# 5_External_interface.net
KiCad netlist of a schematic drawn in Altium Designer
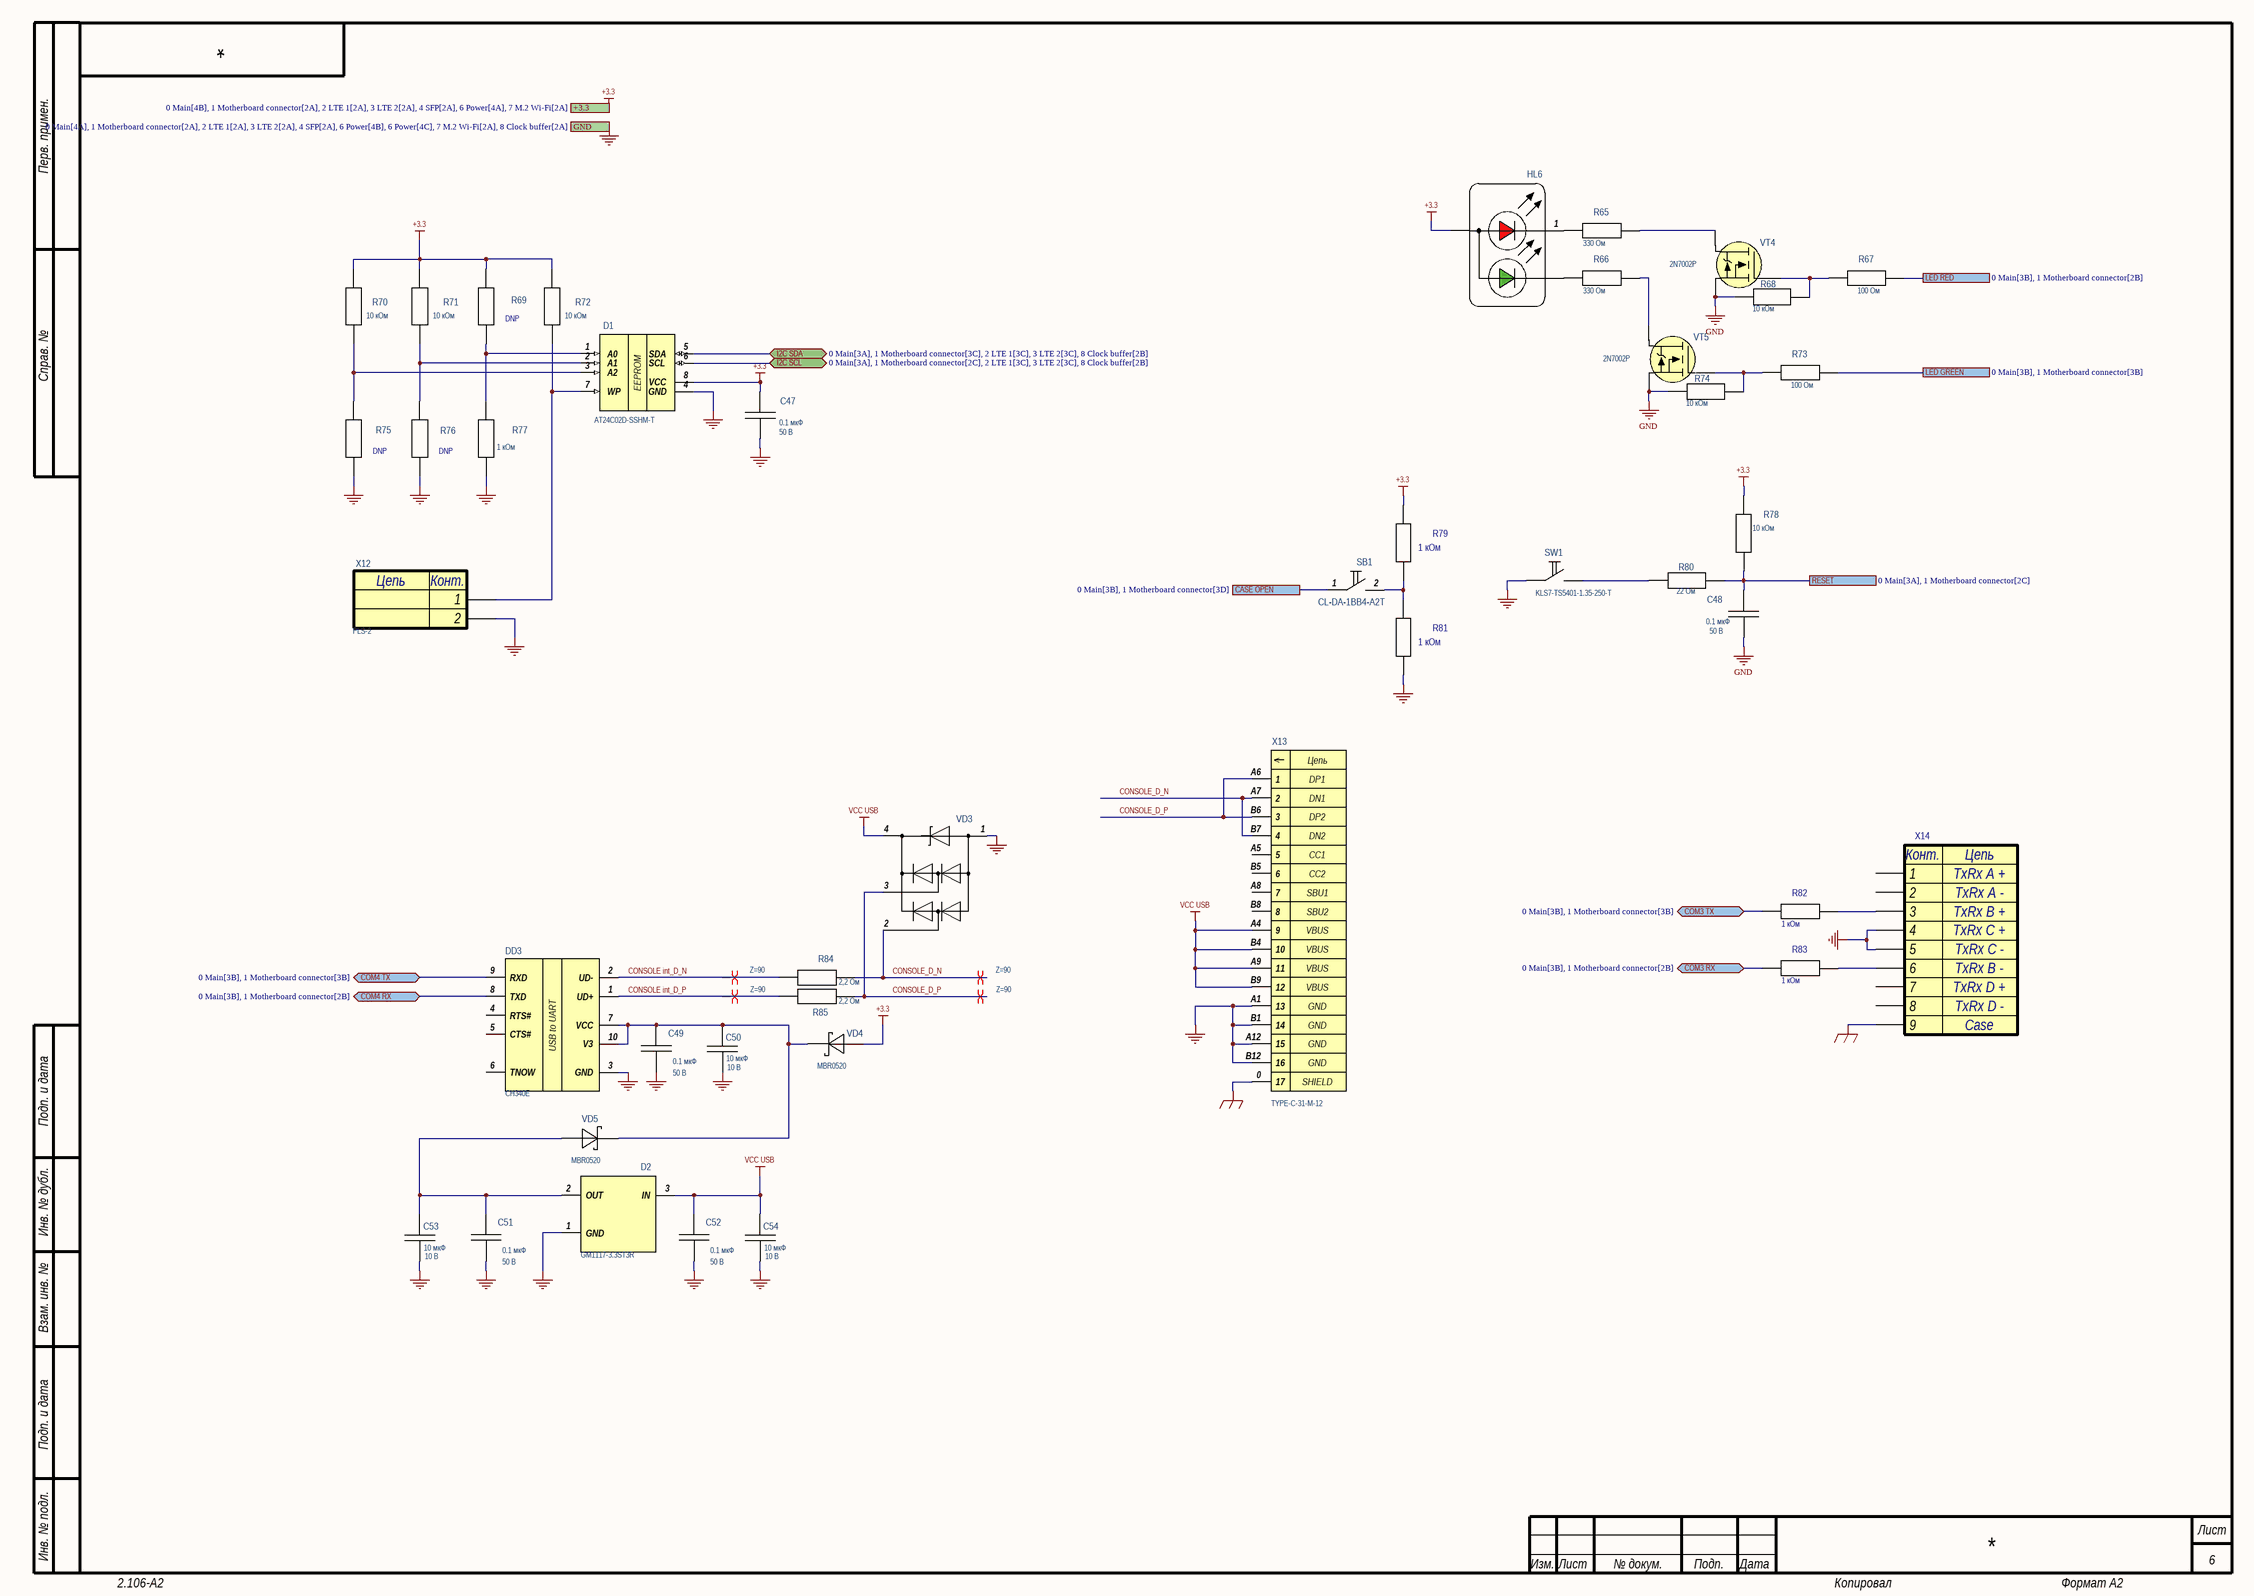
[diagram p0: 5 External interface.SchDoc]

(export (version "E")
  (design (tool "Eeschema 10.0.6"))
  (components
    (comp (ref "C47")
      (value "0.1 мкФ")
      (footprint "CAP_0402")
      (description "Конденсатор CHIP-0402 0.1 мкФ 50 В 10% X7R")
      (fields
        (field (name "PARTNUMBER") "CC0402KRX7R9BB104")
        (field (name "TOLERANCE") "10%")
        (field (name "НАПРЯЖЕНИЕ") "50 В")
        (field (name "AUTOR") "Admin")
      )
      (libsource (lib "Database_Altium") (part "STD_CAP"))
    )
    (comp (ref "C48")
      (value "0.1 мкФ")
      (footprint "CAP_0402")
      (description "Конденсатор CHIP-0402 0.1 мкФ 50 В 10% X7R")
      (fields
        (field (name "PARTNUMBER") "CC0402KRX7R9BB104")
        (field (name "TOLERANCE") "10%")
        (field (name "НАПРЯЖЕНИЕ") "50 В")
        (field (name "AUTOR") "Admin")
      )
      (libsource (lib "Database_Altium") (part "STD_CAP"))
    )
    (comp (ref "C49")
      (value "0.1 мкФ")
      (footprint "CAP_0402")
      (description "Конденсатор CHIP-0402 0.1 мкФ 50 В 10% X7R")
      (fields
        (field (name "PARTNUMBER") "CC0402KRX7R9BB104")
        (field (name "TOLERANCE") "10%")
        (field (name "НАПРЯЖЕНИЕ") "50 В")
        (field (name "AUTOR") "Admin")
      )
      (libsource (lib "Database_Altium") (part "STD_CAP"))
    )
    (comp (ref "C50")
      (value "10 мкФ")
      (footprint "CAP_0603")
      (description "Конденсатор CHIP-0603 10 мкФ 10 В 10% X7R")
      (fields
        (field (name "PARTNUMBER") "GRM188Z71A106KA73D")
        (field (name "TOLERANCE") "10%")
        (field (name "НАПРЯЖЕНИЕ") "10 В")
        (field (name "AUTOR") "Admin")
      )
      (libsource (lib "Database_Altium") (part "STD_CAP"))
    )
    (comp (ref "C51")
      (value "0.1 мкФ")
      (footprint "CAP_0402")
      (description "Конденсатор CHIP-0402 0.1 мкФ 50 В 10% X7R")
      (fields
        (field (name "PARTNUMBER") "CC0402KRX7R9BB104")
        (field (name "TOLERANCE") "10%")
        (field (name "НАПРЯЖЕНИЕ") "50 В")
        (field (name "AUTOR") "Admin")
      )
      (libsource (lib "Database_Altium") (part "STD_CAP"))
    )
    (comp (ref "C52")
      (value "0.1 мкФ")
      (footprint "CAP_0402")
      (description "Конденсатор CHIP-0402 0.1 мкФ 50 В 10% X7R")
      (fields
        (field (name "PARTNUMBER") "CC0402KRX7R9BB104")
        (field (name "TOLERANCE") "10%")
        (field (name "НАПРЯЖЕНИЕ") "50 В")
        (field (name "AUTOR") "Admin")
      )
      (libsource (lib "Database_Altium") (part "STD_CAP"))
    )
    (comp (ref "C53")
      (value "10 мкФ")
      (footprint "CAP_0603")
      (description "Конденсатор CHIP-0603 10 мкФ 10 В 10% X7R")
      (fields
        (field (name "PARTNUMBER") "GRM188Z71A106KA73D")
        (field (name "TOLERANCE") "10%")
        (field (name "НАПРЯЖЕНИЕ") "10 В")
        (field (name "AUTOR") "Admin")
      )
      (libsource (lib "Database_Altium") (part "STD_CAP"))
    )
    (comp (ref "C54")
      (value "10 мкФ")
      (footprint "CAP_0603")
      (description "Конденсатор CHIP-0603 10 мкФ 10 В 10% X7R")
      (fields
        (field (name "PARTNUMBER") "GRM188Z71A106KA73D")
        (field (name "TOLERANCE") "10%")
        (field (name "НАПРЯЖЕНИЕ") "10 В")
        (field (name "AUTOR") "Admin")
      )
      (libsource (lib "Database_Altium") (part "STD_CAP"))
    )
    (comp (ref "D1")
      (value "AT24C02D-SSHM-T")
      (footprint "SOIC-8")
      (description "Микросхема Atmel  EEPROM 2K I2C 1MHZ")
      (fields
        (field (name "VOLTAGE") "1.7-3.6В")
        (field (name "MANUFACTURER") "Atmel")
        (field (name "AUTOR") "Admin")
      )
      (libsource (lib "Database_Altium") (part "AT24C02C"))
    )
    (comp (ref "D2")
      (value "GM1117-3.3ST3R")
      (footprint "SOT-223")
      (description "Микросхема Gamma Electronica  1.0 A Low-Dropout LDO")
      (fields
        (field (name "PARTNUMBER") "GM1117-3.3ST3R")
        (field (name "VOLTAGE") "3.3В")
        (field (name "MANUFACTURER") "Gamma Electronica")
        (field (name "AUTOR") "Admin")
      )
      (libsource (lib "Database_Altium") (part "1117"))
    )
    (comp (ref "DD3")
      (value "CH340E")
      (footprint "MSOP-10")
      (description "Микросхема MPJA USB to UART")
      (fields
        (field (name "VOLTAGE") "5В")
        (field (name "MANUFACTURER") "MPJA")
        (field (name "AUTOR") "Admin")
      )
      (libsource (lib "Database_Altium") (part "CH340E"))
    )
    (comp (ref "HL6")
      (value "LTST-S326KGJRKT")
      (footprint "LTST-S326KGJRKT")
      (description "Диод LITEON 2 В 30 мА")
      (fields (field (name "MANUFACTURER") "LITEON") (field (name "AUTOR") "Admin"))
      (libsource (lib "Database_Altium") (part "LTST-S326KGJRKT"))
    )
    (comp (ref "R65")
      (value "330 Ом")
      (footprint "RES_0402")
      (description "Резистор CHIP-0402 330 Ом 1%")
      (fields
        (field (name "PARTNUMBER") "RC0402FR-07330RL")
        (field (name "TOLERANCE") "1%")
        (field (name "AUTOR") "Цислав А.Н.")
      )
      (libsource (lib "Database_Altium") (part "STD_RES"))
    )
    (comp (ref "R66")
      (value "330 Ом")
      (footprint "RES_0402")
      (description "Резистор CHIP-0402 330 Ом 1%")
      (fields
        (field (name "PARTNUMBER") "RC0402FR-07330RL")
        (field (name "TOLERANCE") "1%")
        (field (name "AUTOR") "Цислав А.Н.")
      )
      (libsource (lib "Database_Altium") (part "STD_RES"))
    )
    (comp (ref "R67")
      (value "100 Ом")
      (footprint "RES_0402")
      (description "Резистор CHIP-0402 100 Ом 1%")
      (fields
        (field (name "PARTNUMBER") "RC0402FR-07100RL")
        (field (name "TOLERANCE") "1%")
        (field (name "AUTOR") "Цислав А.Н.")
      )
      (libsource (lib "Database_Altium") (part "STD_RES"))
    )
    (comp (ref "R68")
      (value "10 кОм")
      (footprint "RES_0402")
      (description "Резистор CHIP-0402 10 кОм 1%")
      (fields
        (field (name "PARTNUMBER") "RC0402FR-0710KL")
        (field (name "TOLERANCE") "1%")
        (field (name "AUTOR") "Цислав А.Н.")
      )
      (libsource (lib "Database_Altium") (part "STD_RES"))
    )
    (comp (ref "R69")
      (value "STD_RES")
      (footprint "RES_0402")
      (description "Резистор CHIP-0402 10 кОм 1%")
      (fields
        (field (name "PARTNUMBER") "RC0402FR-0710KL")
        (field (name "TOLERANCE") "1%")
        (field (name "AUTOR") "Цислав А.Н.")
      )
      (libsource (lib "Database_Altium") (part "STD_RES"))
    )
    (comp (ref "R70")
      (value "10 кОм")
      (footprint "RES_0402")
      (description "Резистор CHIP-0402 10 кОм 1%")
      (fields
        (field (name "PARTNUMBER") "RC0402FR-0710KL")
        (field (name "TOLERANCE") "1%")
        (field (name "AUTOR") "Цислав А.Н.")
      )
      (libsource (lib "Database_Altium") (part "STD_RES"))
    )
    (comp (ref "R71")
      (value "10 кОм")
      (footprint "RES_0402")
      (description "Резистор CHIP-0402 10 кОм 1%")
      (fields
        (field (name "PARTNUMBER") "RC0402FR-0710KL")
        (field (name "TOLERANCE") "1%")
        (field (name "AUTOR") "Цислав А.Н.")
      )
      (libsource (lib "Database_Altium") (part "STD_RES"))
    )
    (comp (ref "R72")
      (value "10 кОм")
      (footprint "RES_0402")
      (description "Резистор CHIP-0402 10 кОм 1%")
      (fields
        (field (name "PARTNUMBER") "RC0402FR-0710KL")
        (field (name "TOLERANCE") "1%")
        (field (name "AUTOR") "Цислав А.Н.")
      )
      (libsource (lib "Database_Altium") (part "STD_RES"))
    )
    (comp (ref "R73")
      (value "100 Ом")
      (footprint "RES_0402")
      (description "Резистор CHIP-0402 100 Ом 1%")
      (fields
        (field (name "PARTNUMBER") "RC0402FR-07100RL")
        (field (name "TOLERANCE") "1%")
        (field (name "AUTOR") "Цислав А.Н.")
      )
      (libsource (lib "Database_Altium") (part "STD_RES"))
    )
    (comp (ref "R74")
      (value "10 кОм")
      (footprint "RES_0402")
      (description "Резистор CHIP-0402 10 кОм 1%")
      (fields
        (field (name "PARTNUMBER") "RC0402FR-0710KL")
        (field (name "TOLERANCE") "1%")
        (field (name "AUTOR") "Цислав А.Н.")
      )
      (libsource (lib "Database_Altium") (part "STD_RES"))
    )
    (comp (ref "R75")
      (value "STD_RES")
      (footprint "RES_0402")
      (description "Резистор CHIP-0402 10 кОм 1%")
      (fields
        (field (name "PARTNUMBER") "RC0402FR-0710KL")
        (field (name "TOLERANCE") "1%")
        (field (name "AUTOR") "Цислав А.Н.")
      )
      (libsource (lib "Database_Altium") (part "STD_RES"))
    )
    (comp (ref "R76")
      (value "STD_RES")
      (footprint "RES_0402")
      (description "Резистор CHIP-0402 10 кОм 1%")
      (fields
        (field (name "PARTNUMBER") "RC0402FR-0710KL")
        (field (name "TOLERANCE") "1%")
        (field (name "AUTOR") "Цислав А.Н.")
      )
      (libsource (lib "Database_Altium") (part "STD_RES"))
    )
    (comp (ref "R77")
      (value "1 кОм")
      (footprint "RES_0402")
      (description "Резистор CHIP-0402 1 кОм 1%")
      (fields
        (field (name "PARTNUMBER") "RC0402FR-071KL")
        (field (name "TOLERANCE") "1%")
        (field (name "AUTOR") "Цислав А.Н.")
      )
      (libsource (lib "Database_Altium") (part "STD_RES"))
    )
    (comp (ref "R78")
      (value "10 кОм")
      (footprint "RES_0402")
      (description "Резистор CHIP-0402 10 кОм 1%")
      (fields
        (field (name "PARTNUMBER") "RC0402FR-0710KL")
        (field (name "TOLERANCE") "1%")
        (field (name "AUTOR") "Цислав А.Н.")
      )
      (libsource (lib "Database_Altium") (part "STD_RES"))
    )
    (comp (ref "R79")
      (value "1 кОм")
      (footprint "RES_0402")
      (description "Резистор CHIP-0402 1 кОм 1%")
      (fields
        (field (name "PARTNUMBER") "RC0402FR-071KL")
        (field (name "TOLERANCE") "1%")
        (field (name "AUTOR") "Цислав А.Н.")
      )
      (libsource (lib "Database_Altium") (part "STD_RES"))
    )
    (comp (ref "R80")
      (value "22 Ом")
      (footprint "RES_0402")
      (description "Резистор CHIP-0402 22 Ом 1%")
      (fields
        (field (name "PARTNUMBER") "RC0402FR-0722RL")
        (field (name "TOLERANCE") "1%")
        (field (name "AUTOR") "Цислав А.Н.")
      )
      (libsource (lib "Database_Altium") (part "STD_RES"))
    )
    (comp (ref "R81")
      (value "1 кОм")
      (footprint "RES_0402")
      (description "Резистор CHIP-0402 1 кОм 1%")
      (fields
        (field (name "PARTNUMBER") "RC0402FR-071KL")
        (field (name "TOLERANCE") "1%")
        (field (name "AUTOR") "Цислав А.Н.")
      )
      (libsource (lib "Database_Altium") (part "STD_RES"))
    )
    (comp (ref "R82")
      (value "1 кОм")
      (footprint "RES_0402")
      (description "Резистор CHIP-0402 1 кОм 5%")
      (fields
        (field (name "PARTNUMBER") "RC0402JR-071KL")
        (field (name "TOLERANCE") "5%")
        (field (name "AUTOR") "Цислав А.Н.")
      )
      (libsource (lib "Database_Altium") (part "STD_RES"))
    )
    (comp (ref "R83")
      (value "1 кОм")
      (footprint "RES_0402")
      (description "Резистор CHIP-0402 1 кОм 5%")
      (fields
        (field (name "PARTNUMBER") "RC0402JR-071KL")
        (field (name "TOLERANCE") "5%")
        (field (name "AUTOR") "Цислав А.Н.")
      )
      (libsource (lib "Database_Altium") (part "STD_RES"))
    )
    (comp (ref "R84")
      (value "2,2 Ом")
      (footprint "RES_0402")
      (description "Резистор CHIP-0402 2,2 Ом 1%")
      (fields
        (field (name "PARTNUMBER") "RC0402FR-072R2L")
        (field (name "TOLERANCE") "1%")
        (field (name "AUTOR") "Admin")
      )
      (libsource (lib "Database_Altium") (part "STD_RES"))
    )
    (comp (ref "R85")
      (value "2,2 Ом")
      (footprint "RES_0402")
      (description "Резистор CHIP-0402 2,2 Ом 1%")
      (fields
        (field (name "PARTNUMBER") "RC0402FR-072R2L")
        (field (name "TOLERANCE") "1%")
        (field (name "AUTOR") "Admin")
      )
      (libsource (lib "Database_Altium") (part "STD_RES"))
    )
    (comp (ref "SB1")
      (value "CL-DA-1BB4-A2T")
      (footprint "CL-DA-1BB4-A2T")
      (description "Copal Electronics  DETECT SWITCH right angle NC")
      (fields
        (field (name "VOLTAGE") "12 B")
        (field (name "MANUFACTURER") "Copal Electronics")
        (field (name "AUTOR") "Admin")
      )
      (libsource (lib "Database_Altium") (part "STD_BUTTON"))
    )
    (comp (ref "SW1")
      (value "KLS7-TS5401-1.35-250-T")
      (footprint "KLS7-TS5401-1.35-250-T")
      (description "KLS Угловая кнопка тактовая SMD")
      (fields
        (field (name "VOLTAGE") "12V")
        (field (name "MANUFACTURER") "KLS")
        (field (name "AUTOR") "Admin")
      )
      (libsource (lib "") (part "STD_BUTTON_1"))
    )
    (comp (ref "VD3")
      (value "WE05R")
      (footprint "SOT143")
      (description "Диод WAYON 5 В 5 А")
      (fields (field (name "MANUFACTURER") "WAYON") (field (name "AUTOR") "Admin"))
      (libsource (lib "Database_Altium") (part "WE05R"))
    )
    (comp (ref "VD4")
      (value "STD_DIODE_SCHOTTKY")
      (footprint "SOD123")
      (description "Диод IR 500 мВ 500 мА")
      (fields
        (field (name "PARTNUMBER") "MBR0520")
        (field (name "MANUFACTURER") "IR")
        (field (name "AUTOR") "Admin")
      )
      (libsource (lib "Database_Altium") (part "STD_DIODE_SCHOTTKY"))
    )
    (comp (ref "VD5")
      (value "STD_DIODE_SCHOTTKY")
      (footprint "SOD123")
      (description "Диод IR 500 мВ 500 мА")
      (fields
        (field (name "PARTNUMBER") "MBR0520")
        (field (name "MANUFACTURER") "IR")
        (field (name "AUTOR") "Admin")
      )
      (libsource (lib "Database_Altium") (part "STD_DIODE_SCHOTTKY"))
    )
    (comp (ref "VT4")
      (value "2N7002P")
      (footprint "SOT-23-3")
      (description "Микросхема NXP  N-channel Trench MOSFET")
      (fields
        (field (name "VOLTAGE") "60В")
        (field (name "MANUFACTURER") "NXP")
        (field (name "AUTOR") "Admin")
      )
      (libsource (lib "Database_Altium") (part "2N7002P"))
    )
    (comp (ref "VT5")
      (value "2N7002P")
      (footprint "SOT-23-3")
      (description "Микросхема NXP  N-channel Trench MOSFET")
      (fields
        (field (name "VOLTAGE") "60В")
        (field (name "MANUFACTURER") "NXP")
        (field (name "AUTOR") "Admin")
      )
      (libsource (lib "Database_Altium") (part "2N7002P"))
    )
    (comp (ref "X12")
      (value "STD_CON2")
      (footprint "PLS-2")
      (description "Разъем NoName PLS")
      (fields
        (field (name "PARTNUMBER") "PLS-2")
        (field (name "MANUFACTURER") "NoName")
        (field (name "CONTACT") "2")
        (field (name "AUTOR") "Admin")
      )
      (libsource (lib "Database_Altium") (part "STD_CON2"))
    )
    (comp (ref "X13")
      (value "TYPE-C-31-M-12")
      (footprint "USB_TYPE_C_16_PIN_TYPE-C-31-M-12")
      (description "Разъем Hroparts Electronics USB")
      (fields
        (field (name "MANUFACTURER") "Hroparts Electronics")
        (field (name "CONTACT") "14")
        (field (name "AUTOR") "Admin")
      )
      (libsource (lib "Database_Altium") (part "USB_TYPE_C_16_PIN"))
    )
    (comp (ref "X14")
      (value "DS1126-S80BP")
      (footprint "DS1126-S80BP")
      (description "Разъем Connfly LAN")
      (fields
        (field (name "MANUFACTURER") "Connfly")
        (field (name "CONTACT") "8")
        (field (name "AUTOR") "Admin")
      )
      (libsource (lib "Database_Altium") (part "6368150-1"))
    )
  )
  (nets
    (net (code "1") (name "+3.3") (class "Default")
      (node (ref "C47") (pin "1") (pinfunction "1_1") (pintype "passive"))
      (node (ref "D1") (pin "8") (pinfunction "VCC_8") (pintype "power_in"))
      (node (ref "HL6") (pin "3") (pinfunction "A_3") (pintype "power_in"))
      (node (ref "R69") (pin "2") (pinfunction "2_2") (pintype "passive"))
      (node (ref "R70") (pin "2") (pinfunction "2_2") (pintype "passive"))
      (node (ref "R71") (pin "2") (pinfunction "2_2") (pintype "passive"))
      (node (ref "R72") (pin "2") (pinfunction "2_2") (pintype "passive"))
      (node (ref "R78") (pin "2") (pinfunction "2_2") (pintype "passive"))
      (node (ref "R79") (pin "1") (pinfunction "1_1") (pintype "passive"))
      (node (ref "VD4") (pin "2") (pinfunction "2_2") (pintype "passive"))
    )
    (net (code "2") (name "/CASE OPEN") (class "Default")
      (node (ref "SB1") (pin "1") (pinfunction "1_1") (pintype "passive"))
    )
    (net (code "3") (name "/COM3 RX") (class "Default")
      (node (ref "R83") (pin "1") (pinfunction "1_1") (pintype "passive"))
    )
    (net (code "4") (name "/COM3 TX") (class "Default")
      (node (ref "R82") (pin "1") (pinfunction "1_1") (pintype "passive"))
    )
    (net (code "5") (name "/COM4 RX") (class "Default")
      (node (ref "DD3") (pin "8") (pinfunction "TXD_8") (pintype "passive"))
    )
    (net (code "6") (name "/COM4 TX") (class "Default")
      (node (ref "DD3") (pin "9") (pinfunction "RXD_9") (pintype "passive"))
    )
    (net (code "7") (name "/CONSOLE int_D_N") (class "Default")
      (node (ref "DD3") (pin "2") (pinfunction "UD-_2") (pintype "passive"))
      (node (ref "R84") (pin "1") (pinfunction "1_1") (pintype "passive"))
    )
    (net (code "8") (name "/CONSOLE int_D_P") (class "Default")
      (node (ref "DD3") (pin "1") (pinfunction "UD+_1") (pintype "passive"))
      (node (ref "R85") (pin "1") (pinfunction "1_1") (pintype "passive"))
    )
    (net (code "9") (name "/CONSOLE_D_N") (class "Default")
      (node (ref "R84") (pin "2") (pinfunction "2_2") (pintype "passive"))
      (node (ref "VD3") (pin "2") (pinfunction "2_2") (pintype "passive"))
      (node (ref "X13") (pin "A7") (pinfunction "2_A7") (pintype "passive"))
      (node (ref "X13") (pin "B7") (pinfunction "4_B7") (pintype "passive"))
    )
    (net (code "10") (name "/CONSOLE_D_P") (class "Default")
      (node (ref "R85") (pin "2") (pinfunction "2_2") (pintype "passive"))
      (node (ref "VD3") (pin "3") (pinfunction "3_3") (pintype "passive"))
      (node (ref "X13") (pin "A6") (pinfunction "1_A6") (pintype "passive"))
      (node (ref "X13") (pin "B6") (pinfunction "3_B6") (pintype "passive"))
    )
    (net (code "11") (name "/I2C SCL") (class "Default")
      (node (ref "D1") (pin "6") (pinfunction "SCL_6") (pintype "bidirectional"))
    )
    (net (code "12") (name "/I2C SDA") (class "Default")
      (node (ref "D1") (pin "5") (pinfunction "SDA_5") (pintype "bidirectional"))
    )
    (net (code "13") (name "/LED GREEN") (class "Default")
      (node (ref "R73") (pin "2") (pinfunction "2_2") (pintype "passive"))
    )
    (net (code "14") (name "/LED RED") (class "Default")
      (node (ref "R67") (pin "2") (pinfunction "2_2") (pintype "passive"))
    )
    (net (code "15") (name "/RESET") (class "Default")
      (node (ref "C48") (pin "1") (pinfunction "1_1") (pintype "passive"))
      (node (ref "R78") (pin "1") (pinfunction "1_1") (pintype "passive"))
      (node (ref "R80") (pin "1") (pinfunction "1_1") (pintype "passive"))
    )
    (net (code "16") (name "GND") (class "Default")
      (node (ref "C47") (pin "2") (pinfunction "2_2") (pintype "passive"))
      (node (ref "C48") (pin "2") (pinfunction "2_2") (pintype "passive"))
      (node (ref "C49") (pin "2") (pinfunction "2_2") (pintype "passive"))
      (node (ref "C50") (pin "2") (pinfunction "2_2") (pintype "passive"))
      (node (ref "C51") (pin "2") (pinfunction "2_2") (pintype "passive"))
      (node (ref "C52") (pin "2") (pinfunction "2_2") (pintype "passive"))
      (node (ref "C53") (pin "2") (pinfunction "2_2") (pintype "passive"))
      (node (ref "C54") (pin "2") (pinfunction "2_2") (pintype "passive"))
      (node (ref "D1") (pin "4") (pinfunction "GND_4") (pintype "power_in"))
      (node (ref "D2") (pin "1") (pinfunction "GND_1") (pintype "power_in"))
      (node (ref "DD3") (pin "3") (pinfunction "GND_3") (pintype "passive"))
      (node (ref "R68") (pin "1") (pinfunction "1_1") (pintype "passive"))
      (node (ref "R74") (pin "1") (pinfunction "1_1") (pintype "passive"))
      (node (ref "R75") (pin "1") (pinfunction "1_1") (pintype "passive"))
      (node (ref "R76") (pin "1") (pinfunction "1_1") (pintype "passive"))
      (node (ref "R77") (pin "1") (pinfunction "1_1") (pintype "passive"))
      (node (ref "R81") (pin "2") (pinfunction "2_2") (pintype "passive"))
      (node (ref "SW1") (pin "1") (pinfunction "1_1") (pintype "passive"))
      (node (ref "VD3") (pin "1") (pinfunction "1_1") (pintype "passive"))
      (node (ref "VT4") (pin "2") (pinfunction "S_2") (pintype "passive"))
      (node (ref "VT5") (pin "2") (pinfunction "S_2") (pintype "passive"))
      (node (ref "X12") (pin "2") (pinfunction "2_2") (pintype "passive"))
      (node (ref "X13") (pin "A1") (pinfunction "13_A1") (pintype "passive"))
      (node (ref "X13") (pin "A12") (pinfunction "15_A12") (pintype "passive"))
      (node (ref "X13") (pin "B1") (pinfunction "14_B1") (pintype "passive"))
      (node (ref "X13") (pin "B12") (pinfunction "16_B12") (pintype "passive"))
      (node (ref "X14") (pin "4") (pinfunction "4_4") (pintype "passive"))
      (node (ref "X14") (pin "5") (pinfunction "5_5") (pintype "passive"))
    )
    (net (code "17") (name "GNDG") (class "Default")
      (node (ref "X13") (pin "0") (pinfunction "17_0") (pintype "passive"))
      (node (ref "X14") (pin "9") (pinfunction "9_9") (pintype "passive"))
    )
    (net (code "18") (name "Net-(D1-A0)") (class "Default")
      (node (ref "D1") (pin "1") (pinfunction "A0_1") (pintype "input"))
      (node (ref "R69") (pin "1") (pinfunction "1_1") (pintype "passive"))
      (node (ref "R77") (pin "2") (pinfunction "2_2") (pintype "passive"))
    )
    (net (code "19") (name "Net-(D1-A1)") (class "Default")
      (node (ref "D1") (pin "2") (pinfunction "A1_2") (pintype "input"))
      (node (ref "R71") (pin "1") (pinfunction "1_1") (pintype "passive"))
      (node (ref "R76") (pin "2") (pinfunction "2_2") (pintype "passive"))
    )
    (net (code "20") (name "Net-(D1-A2)") (class "Default")
      (node (ref "D1") (pin "3") (pinfunction "A2_3") (pintype "input"))
      (node (ref "R70") (pin "1") (pinfunction "1_1") (pintype "passive"))
      (node (ref "R75") (pin "2") (pinfunction "2_2") (pintype "passive"))
    )
    (net (code "21") (name "Net-(D1-WP)") (class "Default")
      (node (ref "D1") (pin "7") (pinfunction "WP_7") (pintype "input"))
      (node (ref "R72") (pin "1") (pinfunction "1_1") (pintype "passive"))
      (node (ref "X12") (pin "1") (pinfunction "1_1") (pintype "passive"))
    )
    (net (code "22") (name "Net-(D2-OUT)") (class "Default")
      (node (ref "C51") (pin "1") (pinfunction "1_1") (pintype "passive"))
      (node (ref "C53") (pin "1") (pinfunction "1_1") (pintype "passive"))
      (node (ref "D2") (pin "2") (pinfunction "OUT_2") (pintype "power_in"))
      (node (ref "VD5") (pin "2") (pinfunction "2_2") (pintype "passive"))
    )
    (net (code "23") (name "Net-(DD3-V3)") (class "Default")
      (node (ref "C49") (pin "1") (pinfunction "1_1") (pintype "passive"))
      (node (ref "C50") (pin "1") (pinfunction "1_1") (pintype "passive"))
      (node (ref "DD3") (pin "10") (pinfunction "V3_10") (pintype "passive"))
      (node (ref "DD3") (pin "7") (pinfunction "VCC_7") (pintype "passive"))
      (node (ref "VD4") (pin "1") (pinfunction "1_1") (pintype "passive"))
      (node (ref "VD5") (pin "1") (pinfunction "1_1") (pintype "passive"))
    )
    (net (code "24") (name "Net-(HL6-K-Pad1)") (class "Default")
      (node (ref "HL6") (pin "1") (pinfunction "K_1") (pintype "power_in"))
      (node (ref "R65") (pin "1") (pinfunction "1_1") (pintype "passive"))
    )
    (net (code "25") (name "Net-(HL6-K-Pad2)") (class "Default")
      (node (ref "HL6") (pin "2") (pinfunction "K_2") (pintype "power_in"))
      (node (ref "R66") (pin "1") (pinfunction "1_1") (pintype "passive"))
    )
    (net (code "26") (name "Net-(R79-Pad2)") (class "Default")
      (node (ref "R79") (pin "2") (pinfunction "2_2") (pintype "passive"))
      (node (ref "R81") (pin "1") (pinfunction "1_1") (pintype "passive"))
      (node (ref "SB1") (pin "2") (pinfunction "2_2") (pintype "passive"))
    )
    (net (code "27") (name "Net-(R80-Pad2)") (class "Default")
      (node (ref "R80") (pin "2") (pinfunction "2_2") (pintype "passive"))
      (node (ref "SW1") (pin "2") (pinfunction "2_2") (pintype "passive"))
    )
    (net (code "28") (name "Net-(R82-Pad2)") (class "Default")
      (node (ref "R82") (pin "2") (pinfunction "2_2") (pintype "passive"))
      (node (ref "X14") (pin "3") (pinfunction "3_3") (pintype "passive"))
    )
    (net (code "29") (name "Net-(R83-Pad2)") (class "Default")
      (node (ref "R83") (pin "2") (pinfunction "2_2") (pintype "passive"))
      (node (ref "X14") (pin "6") (pinfunction "6_6") (pintype "passive"))
    )
    (net (code "30") (name "Net-(VT4-D)") (class "Default")
      (node (ref "R65") (pin "2") (pinfunction "2_2") (pintype "passive"))
      (node (ref "VT4") (pin "3") (pinfunction "D_3") (pintype "passive"))
    )
    (net (code "31") (name "Net-(VT4-G)") (class "Default")
      (node (ref "R67") (pin "1") (pinfunction "1_1") (pintype "passive"))
      (node (ref "R68") (pin "2") (pinfunction "2_2") (pintype "passive"))
      (node (ref "VT4") (pin "1") (pinfunction "G_1") (pintype "passive"))
    )
    (net (code "32") (name "Net-(VT5-D)") (class "Default")
      (node (ref "R66") (pin "2") (pinfunction "2_2") (pintype "passive"))
      (node (ref "VT5") (pin "3") (pinfunction "D_3") (pintype "passive"))
    )
    (net (code "33") (name "Net-(VT5-G)") (class "Default")
      (node (ref "R73") (pin "1") (pinfunction "1_1") (pintype "passive"))
      (node (ref "R74") (pin "2") (pinfunction "2_2") (pintype "passive"))
      (node (ref "VT5") (pin "1") (pinfunction "G_1") (pintype "passive"))
    )
    (net (code "34") (name "VCC USB") (class "Default")
      (node (ref "C52") (pin "1") (pinfunction "1_1") (pintype "passive"))
      (node (ref "C54") (pin "1") (pinfunction "1_1") (pintype "passive"))
      (node (ref "D2") (pin "3") (pinfunction "IN_3") (pintype "power_in"))
      (node (ref "VD3") (pin "4") (pinfunction "4_4") (pintype "passive"))
      (node (ref "X13") (pin "A4") (pinfunction "9_A4") (pintype "passive"))
      (node (ref "X13") (pin "A9") (pinfunction "11_A9") (pintype "passive"))
      (node (ref "X13") (pin "B4") (pinfunction "10_B4") (pintype "passive"))
      (node (ref "X13") (pin "B9") (pinfunction "12_B9") (pintype "passive"))
    )
    (net (code "35") (name "unconnected-(DD3-CTS#-Pad5)") (class "Default")
      (node (ref "DD3") (pin "5") (pinfunction "CTS#_5") (pintype "passive"))
    )
    (net (code "36") (name "unconnected-(DD3-RTS#-Pad4)") (class "Default")
      (node (ref "DD3") (pin "4") (pinfunction "RTS#_4") (pintype "passive"))
    )
    (net (code "37") (name "unconnected-(DD3-TNOW-Pad6)") (class "Default")
      (node (ref "DD3") (pin "6") (pinfunction "TNOW_6") (pintype "passive"))
    )
    (net (code "38") (name "unconnected-(X13-5-PadA5)") (class "Default")
      (node (ref "X13") (pin "A5") (pinfunction "5_A5") (pintype "passive"))
    )
    (net (code "39") (name "unconnected-(X13-6-PadB5)") (class "Default")
      (node (ref "X13") (pin "B5") (pinfunction "6_B5") (pintype "passive"))
    )
    (net (code "40") (name "unconnected-(X13-7-PadA8)") (class "Default")
      (node (ref "X13") (pin "A8") (pinfunction "7_A8") (pintype "passive"))
    )
    (net (code "41") (name "unconnected-(X13-8-PadB8)") (class "Default")
      (node (ref "X13") (pin "B8") (pinfunction "8_B8") (pintype "passive"))
    )
    (net (code "42") (name "unconnected-(X14-Pad1)") (class "Default")
      (node (ref "X14") (pin "1") (pinfunction "1_1") (pintype "passive"))
    )
    (net (code "43") (name "unconnected-(X14-Pad2)") (class "Default")
      (node (ref "X14") (pin "2") (pinfunction "2_2") (pintype "passive"))
    )
    (net (code "44") (name "unconnected-(X14-Pad7)") (class "Default")
      (node (ref "X14") (pin "7") (pinfunction "7_7") (pintype "passive"))
    )
    (net (code "45") (name "unconnected-(X14-Pad8)") (class "Default")
      (node (ref "X14") (pin "8") (pinfunction "8_8") (pintype "passive"))
    )
  )
)
